# Sheet2.net
KiCad netlist of a schematic drawn in Altium Designer
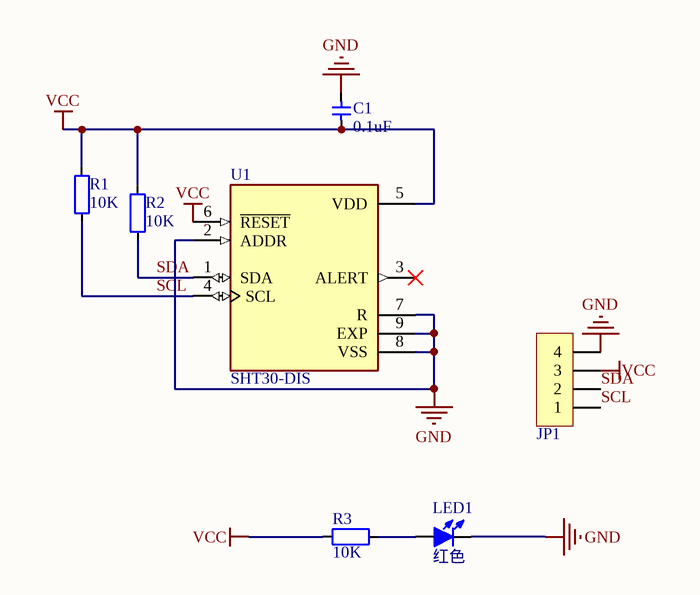
[diagram p0: Sheet2.SchDoc]

(export (version "E")
  (design (tool "Eeschema 10.0.6"))
  (components
    (comp (ref "C1")
      (value "0.1uF")
      (footprint "CAP_0402")
      (description "Capacitor")
      (libsource (lib "Capacitance") (part "电容-0402"))
    )
    (comp (ref "JP1")
      (value "HDR-1X4")
      (footprint "HDR2.54-LI-4P")
      (description "4P接插件")
      (libsource (lib "5.5 - 2.54mm(100mil)连接器(XH2.54)") (part "Header 4"))
    )
    (comp (ref "LED1")
      (value "红色")
      (footprint "LED0603_R")
      (description "贴片LED")
      (libsource (lib "0.3 - LED发光二极管-IR二极管_接收管-光耦") (part "LED-SMD"))
    )
    (comp (ref "R1")
      (value "10K")
      (footprint "RES_0402")
      (description "Resistor")
      (libsource (lib "Resistance") (part "电阻-0402"))
    )
    (comp (ref "R2")
      (value "10K")
      (footprint "RES_0402")
      (description "Resistor")
      (libsource (lib "Resistance") (part "电阻-0402"))
    )
    (comp (ref "R3")
      (value "10K")
      (footprint "RES_0402")
      (description "Resistor")
      (libsource (lib "") (part "电阻-0402_1"))
    )
    (comp (ref "U1")
      (value "SHT30-DIS")
      (footprint "DFN250X250X100-9N")
      (description "SHT3x Series 5.5 V 卤3 %RH 0 to 100% Temperature and Humidity Sensor - DFN-8")
      (fields (field (name "MF") "{'manufacturer': u'Sensirion AG'}"))
      (libsource (lib "Temperature") (part "SHT30-DIS"))
    )
  )
  (nets
    (net (code "1") (name "/SCL") (class "Default")
      (node (ref "JP1") (pin "1") (pinfunction "1_1") (pintype "passive"))
      (node (ref "R1") (pin "1") (pinfunction "1_1") (pintype "passive"))
      (node (ref "U1") (pin "4") (pinfunction "SCL_4") (pintype "bidirectional"))
    )
    (net (code "2") (name "/SDA") (class "Default")
      (node (ref "JP1") (pin "2") (pinfunction "2_2") (pintype "passive"))
      (node (ref "R2") (pin "1") (pinfunction "1_1") (pintype "passive"))
      (node (ref "U1") (pin "1") (pinfunction "SDA_1") (pintype "bidirectional"))
    )
    (net (code "3") (name "GND") (class "Default")
      (node (ref "C1") (pin "2") (pinfunction "2_2") (pintype "passive"))
      (node (ref "JP1") (pin "4") (pinfunction "4_4") (pintype "passive"))
      (node (ref "LED1") (pin "2") (pinfunction "K_2") (pintype "passive"))
      (node (ref "U1") (pin "2") (pinfunction "ADDR_2") (pintype "input"))
      (node (ref "U1") (pin "7") (pinfunction "R_7") (pintype "passive"))
      (node (ref "U1") (pin "8") (pinfunction "VSS_8") (pintype "passive"))
      (node (ref "U1") (pin "9") (pinfunction "EXP_9") (pintype "passive"))
    )
    (net (code "4") (name "Net-(LED1-A)") (class "Default")
      (node (ref "LED1") (pin "1") (pinfunction "A_1") (pintype "passive"))
      (node (ref "R3") (pin "1") (pinfunction "1_1") (pintype "passive"))
    )
    (net (code "5") (name "VCC") (class "Default")
      (node (ref "C1") (pin "1") (pinfunction "1_1") (pintype "passive"))
      (node (ref "JP1") (pin "3") (pinfunction "3_3") (pintype "passive"))
      (node (ref "R1") (pin "2") (pinfunction "2_2") (pintype "passive"))
      (node (ref "R2") (pin "2") (pinfunction "2_2") (pintype "passive"))
      (node (ref "R3") (pin "2") (pinfunction "2_2") (pintype "passive"))
      (node (ref "U1") (pin "5") (pinfunction "VDD_5") (pintype "power_in"))
      (node (ref "U1") (pin "6") (pinfunction "~{RESET}_6") (pintype "input"))
    )
    (net (code "6") (name "unconnected-(U1-ALERT-Pad3)") (class "Default")
      (node (ref "U1") (pin "3") (pinfunction "ALERT_3") (pintype "output+no_connect"))
    )
  )
)
